# IR_Sensor.net
KiCad netlist of a schematic drawn in EAGLE
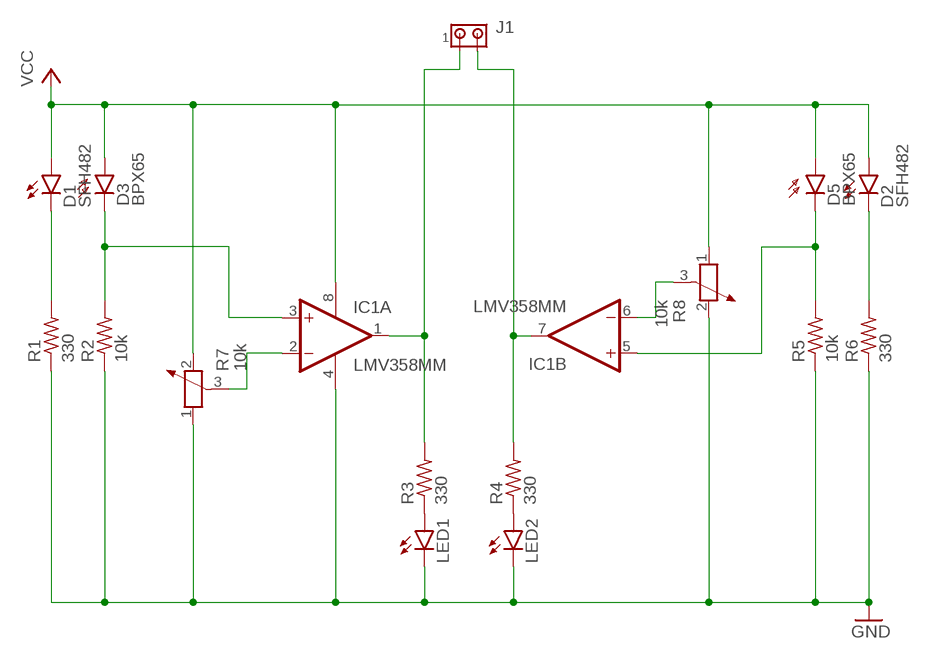
[diagram p0: schematic, sheet 1]

(export (version "E")
  (design (tool "Eeschema 10.0.6"))
  (components
    (comp (ref "D1")
      (value "SFH482")
      (footprint "eagle-import:SFH482")
      (libsource (lib "eagle-import") (part "SFH482"))
    )
    (comp (ref "D2")
      (value "SFH482")
      (footprint "eagle-import:SFH482")
      (libsource (lib "eagle-import") (part "SFH482"))
    )
    (comp (ref "D3")
      (value "BPX65")
      (footprint "eagle-import:BPX65")
      (fields (field (name "MPN") "BPX65."))
      (libsource (lib "eagle-import") (part "BPX65"))
    )
    (comp (ref "D5")
      (value "BPX65")
      (footprint "eagle-import:BPX65")
      (fields (field (name "MPN") "BPX65."))
      (libsource (lib "eagle-import") (part "BPX65"))
    )
    (comp (ref "IC1")
      (value "LMV358MM")
      (footprint "eagle-import:MSOP08")
      (libsource (lib "eagle-import") (part "LMV358?MM"))
    )
    (comp (ref "J1")
      (value "MTA02-100")
      (footprint "eagle-import:10X02MTA")
      (libsource (lib "eagle-import") (part "MTA02-100"))
    )
    (comp (ref "LED1")
      (value "LED3MM")
      (footprint "eagle-import:LED3MM")
      (libsource (lib "eagle-import") (part "LED3MM"))
    )
    (comp (ref "LED2")
      (value "LED3MM")
      (footprint "eagle-import:LED3MM")
      (libsource (lib "eagle-import") (part "LED3MM"))
    )
    (comp (ref "R1")
      (value "330")
      (footprint "eagle-import:R0603")
      (libsource (lib "eagle-import") (part "R-US_R0603"))
    )
    (comp (ref "R2")
      (value "10k")
      (footprint "eagle-import:R0603")
      (libsource (lib "eagle-import") (part "R-US_R0603"))
    )
    (comp (ref "R3")
      (value "330")
      (footprint "eagle-import:R0603")
      (libsource (lib "eagle-import") (part "R-US_R0603"))
    )
    (comp (ref "R4")
      (value "330")
      (footprint "eagle-import:R0603")
      (libsource (lib "eagle-import") (part "R-US_R0603"))
    )
    (comp (ref "R5")
      (value "10k")
      (footprint "eagle-import:R0603")
      (libsource (lib "eagle-import") (part "R-US_R0603"))
    )
    (comp (ref "R6")
      (value "330")
      (footprint "eagle-import:R0603")
      (libsource (lib "eagle-import") (part "R-US_R0603"))
    )
    (comp (ref "R7")
      (value "10k")
      (footprint "eagle-import:PT-10")
      (libsource (lib "eagle-import") (part "POTENTIOMETER_PT-10"))
    )
    (comp (ref "R8")
      (value "10k")
      (footprint "eagle-import:PT-10")
      (libsource (lib "eagle-import") (part "POTENTIOMETER_PT-10"))
    )
  )
  (nets
    (net (code "1") (name "GND") (class "Default")
      (node (ref "IC1") (pin "4") (pinfunction "V-_4") (pintype "power_in"))
      (node (ref "LED1") (pin "K") (pinfunction "C_K") (pintype "passive"))
      (node (ref "LED2") (pin "K") (pinfunction "C_K") (pintype "passive"))
      (node (ref "R1") (pin "1") (pinfunction "1_1") (pintype "passive"))
      (node (ref "R2") (pin "1") (pinfunction "1_1") (pintype "passive"))
      (node (ref "R5") (pin "1") (pinfunction "1_1") (pintype "passive"))
      (node (ref "R6") (pin "1") (pinfunction "1_1") (pintype "passive"))
      (node (ref "R7") (pin "1") (pinfunction "1_1") (pintype "passive"))
      (node (ref "R8") (pin "2") (pinfunction "2_2") (pintype "passive"))
    )
    (net (code "2") (name "Net-(D1-C)") (class "Default")
      (node (ref "D1") (pin "K") (pinfunction "C_K") (pintype "passive"))
      (node (ref "R1") (pin "2") (pinfunction "2_2") (pintype "passive"))
    )
    (net (code "3") (name "Net-(D2-C)") (class "Default")
      (node (ref "D2") (pin "K") (pinfunction "C_K") (pintype "passive"))
      (node (ref "R6") (pin "2") (pinfunction "2_2") (pintype "passive"))
    )
    (net (code "4") (name "Net-(D3-C)") (class "Default")
      (node (ref "D3") (pin "K") (pinfunction "C_K") (pintype "passive"))
      (node (ref "IC1") (pin "3") (pinfunction "+IN_3") (pintype "input"))
      (node (ref "R2") (pin "2") (pinfunction "2_2") (pintype "passive"))
    )
    (net (code "5") (name "Net-(D5-C)") (class "Default")
      (node (ref "D5") (pin "K") (pinfunction "C_K") (pintype "passive"))
      (node (ref "IC1") (pin "5") (pinfunction "+IN_5") (pintype "input"))
      (node (ref "R5") (pin "2") (pinfunction "2_2") (pintype "passive"))
    )
    (net (code "6") (name "Net-(IC1A--IN)") (class "Default")
      (node (ref "IC1") (pin "2") (pinfunction "-IN_2") (pintype "input"))
      (node (ref "R7") (pin "3") (pinfunction "3_3") (pintype "passive"))
    )
    (net (code "7") (name "Net-(IC1A-OUT)") (class "Default")
      (node (ref "IC1") (pin "1") (pinfunction "OUT_1") (pintype "output"))
      (node (ref "J1") (pin "1") (pinfunction "1_1") (pintype "passive"))
      (node (ref "R3") (pin "2") (pinfunction "2_2") (pintype "passive"))
    )
    (net (code "8") (name "Net-(IC1B--IN)") (class "Default")
      (node (ref "IC1") (pin "6") (pinfunction "-IN_6") (pintype "input"))
      (node (ref "R8") (pin "3") (pinfunction "3_3") (pintype "passive"))
    )
    (net (code "9") (name "Net-(IC1B-OUT)") (class "Default")
      (node (ref "IC1") (pin "7") (pinfunction "OUT_7") (pintype "output"))
      (node (ref "J1") (pin "2") (pinfunction "2_2") (pintype "passive"))
      (node (ref "R4") (pin "2") (pinfunction "2_2") (pintype "passive"))
    )
    (net (code "10") (name "Net-(LED1-PadA)") (class "Default")
      (node (ref "LED1") (pin "A") (pinfunction "A_A") (pintype "passive"))
      (node (ref "R3") (pin "1") (pinfunction "1_1") (pintype "passive"))
    )
    (net (code "11") (name "Net-(LED2-PadA)") (class "Default")
      (node (ref "LED2") (pin "A") (pinfunction "A_A") (pintype "passive"))
      (node (ref "R4") (pin "1") (pinfunction "1_1") (pintype "passive"))
    )
    (net (code "12") (name "VCC") (class "Default")
      (node (ref "D1") (pin "A") (pinfunction "A_A") (pintype "passive"))
      (node (ref "D2") (pin "A") (pinfunction "A_A") (pintype "passive"))
      (node (ref "D3") (pin "A") (pinfunction "A_A") (pintype "passive"))
      (node (ref "D5") (pin "A") (pinfunction "A_A") (pintype "passive"))
      (node (ref "IC1") (pin "8") (pinfunction "V+_8") (pintype "power_in"))
      (node (ref "R7") (pin "2") (pinfunction "2_2") (pintype "passive"))
      (node (ref "R8") (pin "1") (pinfunction "1_1") (pintype "passive"))
    )
  )
)
